# Gate_Drive.net
KiCad netlist of a schematic drawn in Altium Designer
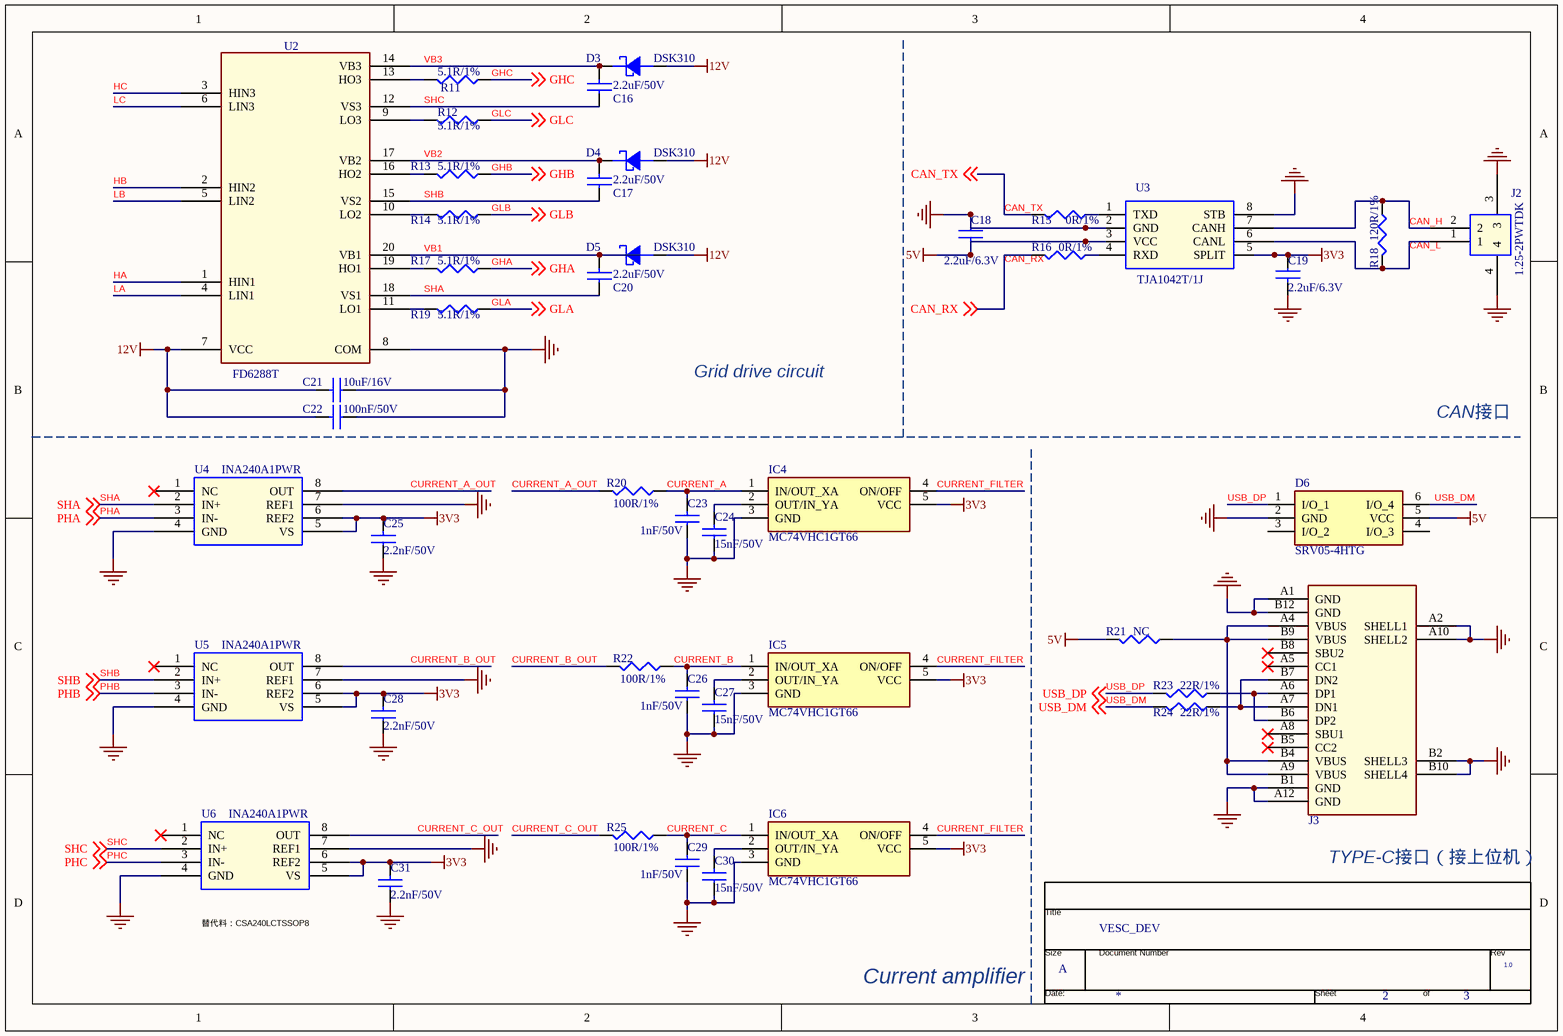
[diagram p0: Gate_Drive.SchDoc]

(export (version "E")
  (design (tool "Eeschema 10.0.6"))
  (components
    (comp (ref "C16") (value "2.2uF/50V") (footprint "C0603") (libsource (lib "*") (part "CAP NP")))
    (comp (ref "C17") (value "2.2uF/50V") (footprint "C0603") (libsource (lib "*") (part "CAP NP")))
    (comp (ref "C18") (value "2.2uF/6.3V") (footprint "C0402") (libsource (lib "*") (part "CAP NP")))
    (comp (ref "C19") (value "2.2uF/6.3V") (footprint "C0402") (libsource (lib "*") (part "CAP NP")))
    (comp (ref "C20") (value "2.2uF/50V") (footprint "C0603") (libsource (lib "*") (part "CAP NP")))
    (comp (ref "C21") (value "10uF/16V") (footprint "C0603") (libsource (lib "*") (part "CAP NP")))
    (comp (ref "C22") (value "100nF/50V") (footprint "C0402") (libsource (lib "*") (part "CAP NP")))
    (comp (ref "C23") (value "1nF/50V") (footprint "C0402") (libsource (lib "*") (part "CAP NP")))
    (comp (ref "C24") (value "15nF/50V") (footprint "C0402") (libsource (lib "*") (part "CAP NP")))
    (comp (ref "C25") (value "2.2nF/50V") (footprint "C0402") (libsource (lib "*") (part "CAP NP")))
    (comp (ref "C26") (value "1nF/50V") (footprint "C0402") (libsource (lib "*") (part "CAP NP")))
    (comp (ref "C27") (value "15nF/50V") (footprint "C0402") (libsource (lib "*") (part "CAP NP")))
    (comp (ref "C28") (value "2.2nF/50V") (footprint "C0402") (libsource (lib "*") (part "CAP NP")))
    (comp (ref "C29") (value "1nF/50V") (footprint "C0402") (libsource (lib "*") (part "CAP NP")))
    (comp (ref "C30") (value "15nF/50V") (footprint "C0402") (libsource (lib "*") (part "CAP NP")))
    (comp (ref "C31") (value "2.2nF/50V") (footprint "C0402") (libsource (lib "*") (part "CAP NP")))
    (comp (ref "D3") (value "DSK310") (footprint "SOD-123F") (libsource (lib "*") (part "DIODE SCHOTTKY21")))
    (comp (ref "D4") (value "DSK310") (footprint "SOD-123F") (libsource (lib "*") (part "DIODE SCHOTTKY21")))
    (comp (ref "D5") (value "DSK310") (footprint "SOD-123F") (libsource (lib "*") (part "DIODE SCHOTTKY21")))
    (comp (ref "D6")
      (value "SRV05-4HTG")
      (footprint "SamacSys:SOT95P280X145-6N")
      (description "TVS Diode (Uni-directional)")
      (fields (field (name "MOUSER PART NUMBER") "576-SRV05-4HTG"))
      (libsource (lib "VESC_DEVICE_Library") (part "SRV05-4HTG"))
    )
    (comp (ref "IC4")
      (value "MC74VHC1GT66")
      (footprint "SamacSys:SOT95P275X110-5N")
      (description "Integrated Circuit")
      (libsource (lib "VESC_DEVICE_Library") (part "MC74VHC1GT66"))
    )
    (comp (ref "IC5")
      (value "MC74VHC1GT66")
      (footprint "SamacSys:SOT95P275X110-5N")
      (description "Integrated Circuit")
      (libsource (lib "VESC_DEVICE_Library") (part "MC74VHC1GT66"))
    )
    (comp (ref "IC6")
      (value "MC74VHC1GT66")
      (footprint "SamacSys:SOT95P275X110-5N")
      (description "Integrated Circuit")
      (libsource (lib "VESC_DEVICE_Library") (part "MC74VHC1GT66"))
    )
    (comp (ref "J2")
      (value "1.25-2PWTDK")
      (footprint "SMD-2P-1_25")
      (libsource (lib "*") (part "1.25-2PWTDK"))
    )
    (comp (ref "J3")
      (value "TYPE-C 16PLC-H10.0")
      (footprint "TYPE-C-TH_16PLC-H10.0")
      (description "连接器类型:Type-C;标准:USB 3.1;公母:母;安装方式:直插;触点数量:16P;端口数量:1;额定电流 - 电源:5A;触头材质:-;触头镀层:-;工作温度范围:-40℃~+85℃;")
      (fields (field (name "MANUFACTURER") "SHOU HAN(首韩)"))
      (libsource (lib "VESC_DEVICE_Library") (part "TYPE-C 16PLC-H10.0"))
    )
    (comp (ref "R11") (value "5.1R/1%") (footprint "R0603") (libsource (lib "*") (part "RESISTOR")))
    (comp (ref "R12") (value "5.1R/1%") (footprint "R0603") (libsource (lib "*") (part "RESISTOR")))
    (comp (ref "R13") (value "5.1R/1%") (footprint "R0603") (libsource (lib "*") (part "RESISTOR")))
    (comp (ref "R14") (value "5.1R/1%") (footprint "R0603") (libsource (lib "*") (part "RESISTOR")))
    (comp (ref "R15") (value "0R/1%") (footprint "R0402") (libsource (lib "*") (part "RESISTOR")))
    (comp (ref "R16") (value "0R/1%") (footprint "R0402") (libsource (lib "*") (part "RESISTOR")))
    (comp (ref "R17") (value "5.1R/1%") (footprint "R0603") (libsource (lib "*") (part "RESISTOR")))
    (comp (ref "R18") (value "120R/1%") (footprint "R0402") (libsource (lib "*") (part "RESISTOR")))
    (comp (ref "R19") (value "5.1R/1%") (footprint "R0603") (libsource (lib "*") (part "RESISTOR")))
    (comp (ref "R20") (value "100R/1%") (footprint "R0402") (libsource (lib "*") (part "RESISTOR")))
    (comp (ref "R21") (value "NC") (footprint "R0603") (libsource (lib "*") (part "RESISTOR")))
    (comp (ref "R22") (value "100R/1%") (footprint "R0402") (libsource (lib "*") (part "RESISTOR")))
    (comp (ref "R23") (value "22R/1%") (footprint "R0402") (libsource (lib "*") (part "RESISTOR")))
    (comp (ref "R24") (value "22R/1%") (footprint "R0402") (libsource (lib "*") (part "RESISTOR")))
    (comp (ref "R25") (value "100R/1%") (footprint "R0402") (libsource (lib "*") (part "RESISTOR")))
    (comp (ref "U2")
      (value "FD6288T")
      (footprint "TSSOP-20")
      (libsource (lib "VESC_DEVICE_Library") (part "FD6288T"))
    )
    (comp (ref "U3") (value "TJA1042T/1J") (footprint "SOP-8") (libsource (lib "*") (part "TJA1042T/1J")))
    (comp (ref "U4") (value "INA240A1PWR") (footprint "TSSOP-8") (libsource (lib "*") (part "INA240A1PWR")))
    (comp (ref "U5") (value "INA240A1PWR") (footprint "TSSOP-8") (libsource (lib "*") (part "INA240A1PWR")))
    (comp (ref "U6") (value "INA240A1PWR") (footprint "TSSOP-8") (libsource (lib "*") (part "INA240A1PWR")))
  )
  (nets
    (net (code "1") (name "/CAN_H") (class "Default")
      (node (ref "J2") (pin "2") (pinfunction "2_2") (pintype "passive"))
      (node (ref "R18") (pin "1") (pinfunction "1_1") (pintype "passive"))
      (node (ref "U3") (pin "7") (pinfunction "CANH_7") (pintype "passive"))
    )
    (net (code "2") (name "/CAN_L") (class "Default")
      (node (ref "J2") (pin "1") (pinfunction "1_1") (pintype "passive"))
      (node (ref "R18") (pin "2") (pinfunction "2_2") (pintype "passive"))
      (node (ref "U3") (pin "6") (pinfunction "CANL_6") (pintype "passive"))
    )
    (net (code "3") (name "/CURRENT_A") (class "Default")
      (node (ref "C23") (pin "2") (pinfunction "2_2") (pintype "passive"))
      (node (ref "IC4") (pin "1") (pinfunction "IN/OUT_XA_1") (pintype "passive"))
      (node (ref "R20") (pin "1") (pinfunction "1_1") (pintype "passive"))
    )
    (net (code "4") (name "/CURRENT_A_OUT") (class "Default")
      (node (ref "R20") (pin "2") (pinfunction "2_2") (pintype "passive"))
      (node (ref "U4") (pin "8") (pinfunction "OUT_8") (pintype "passive"))
    )
    (net (code "5") (name "/CURRENT_B") (class "Default")
      (node (ref "C26") (pin "2") (pinfunction "2_2") (pintype "passive"))
      (node (ref "IC5") (pin "1") (pinfunction "IN/OUT_XA_1") (pintype "passive"))
      (node (ref "R22") (pin "1") (pinfunction "1_1") (pintype "passive"))
    )
    (net (code "6") (name "/CURRENT_B_OUT") (class "Default")
      (node (ref "R22") (pin "2") (pinfunction "2_2") (pintype "passive"))
      (node (ref "U5") (pin "8") (pinfunction "OUT_8") (pintype "passive"))
    )
    (net (code "7") (name "/CURRENT_C") (class "Default")
      (node (ref "C29") (pin "2") (pinfunction "2_2") (pintype "passive"))
      (node (ref "IC6") (pin "1") (pinfunction "IN/OUT_XA_1") (pintype "passive"))
      (node (ref "R25") (pin "1") (pinfunction "1_1") (pintype "passive"))
    )
    (net (code "8") (name "/CURRENT_C_OUT") (class "Default")
      (node (ref "R25") (pin "2") (pinfunction "2_2") (pintype "passive"))
      (node (ref "U6") (pin "8") (pinfunction "OUT_8") (pintype "passive"))
    )
    (net (code "9") (name "/CURRENT_FILTER") (class "Default")
      (node (ref "IC4") (pin "4") (pinfunction "ON/OFF_4") (pintype "passive"))
      (node (ref "IC5") (pin "4") (pinfunction "ON/OFF_4") (pintype "passive"))
      (node (ref "IC6") (pin "4") (pinfunction "ON/OFF_4") (pintype "passive"))
    )
    (net (code "10") (name "/HA") (class "Default")
      (node (ref "U2") (pin "1") (pinfunction "HIN1_1") (pintype "passive"))
    )
    (net (code "11") (name "/HB") (class "Default")
      (node (ref "U2") (pin "2") (pinfunction "HIN2_2") (pintype "passive"))
    )
    (net (code "12") (name "/HC") (class "Default")
      (node (ref "U2") (pin "3") (pinfunction "HIN3_3") (pintype "passive"))
    )
    (net (code "13") (name "/LA") (class "Default")
      (node (ref "U2") (pin "4") (pinfunction "LIN1_4") (pintype "passive"))
    )
    (net (code "14") (name "/LB") (class "Default")
      (node (ref "U2") (pin "5") (pinfunction "LIN2_5") (pintype "passive"))
    )
    (net (code "15") (name "/LC") (class "Default")
      (node (ref "U2") (pin "6") (pinfunction "LIN3_6") (pintype "passive"))
    )
    (net (code "16") (name "/VB1") (class "Default")
      (node (ref "C20") (pin "2") (pinfunction "2_2") (pintype "passive"))
      (node (ref "D5") (pin "1") (pinfunction "K_1") (pintype "passive"))
      (node (ref "U2") (pin "20") (pinfunction "VB1_20") (pintype "passive"))
    )
    (net (code "17") (name "/VB2") (class "Default")
      (node (ref "C17") (pin "2") (pinfunction "2_2") (pintype "passive"))
      (node (ref "D4") (pin "1") (pinfunction "K_1") (pintype "passive"))
      (node (ref "U2") (pin "17") (pinfunction "VB2_17") (pintype "passive"))
    )
    (net (code "18") (name "/VB3") (class "Default")
      (node (ref "C16") (pin "2") (pinfunction "2_2") (pintype "passive"))
      (node (ref "D3") (pin "1") (pinfunction "K_1") (pintype "passive"))
      (node (ref "U2") (pin "14") (pinfunction "VB3_14") (pintype "passive"))
    )
    (net (code "19") (name "3V3") (class "Default")
      (node (ref "C19") (pin "1") (pinfunction "1_1") (pintype "passive"))
      (node (ref "C25") (pin "2") (pinfunction "2_2") (pintype "passive"))
      (node (ref "C28") (pin "2") (pinfunction "2_2") (pintype "passive"))
      (node (ref "C31") (pin "2") (pinfunction "2_2") (pintype "passive"))
      (node (ref "IC4") (pin "5") (pinfunction "VCC_5") (pintype "passive"))
      (node (ref "IC5") (pin "5") (pinfunction "VCC_5") (pintype "passive"))
      (node (ref "IC6") (pin "5") (pinfunction "VCC_5") (pintype "passive"))
      (node (ref "U3") (pin "5") (pinfunction "SPLIT_5") (pintype "passive"))
      (node (ref "U4") (pin "5") (pinfunction "VS_5") (pintype "passive"))
      (node (ref "U4") (pin "6") (pinfunction "REF2_6") (pintype "passive"))
      (node (ref "U5") (pin "5") (pinfunction "VS_5") (pintype "passive"))
      (node (ref "U5") (pin "6") (pinfunction "REF2_6") (pintype "passive"))
      (node (ref "U6") (pin "5") (pinfunction "VS_5") (pintype "passive"))
      (node (ref "U6") (pin "6") (pinfunction "REF2_6") (pintype "passive"))
    )
    (net (code "20") (name "5V") (class "Default")
      (node (ref "C18") (pin "2") (pinfunction "2_2") (pintype "passive"))
      (node (ref "D6") (pin "5") (pinfunction "VCC_5") (pintype "passive"))
      (node (ref "R21") (pin "2") (pinfunction "2_2") (pintype "passive"))
      (node (ref "U3") (pin "3") (pinfunction "VCC_3") (pintype "passive"))
    )
    (net (code "21") (name "12V") (class "Default")
      (node (ref "C21") (pin "2") (pinfunction "2_2") (pintype "passive"))
      (node (ref "C22") (pin "2") (pinfunction "2_2") (pintype "passive"))
      (node (ref "D3") (pin "2") (pinfunction "A_2") (pintype "passive"))
      (node (ref "D4") (pin "2") (pinfunction "A_2") (pintype "passive"))
      (node (ref "D5") (pin "2") (pinfunction "A_2") (pintype "passive"))
      (node (ref "U2") (pin "7") (pinfunction "VCC_7") (pintype "power_in"))
    )
    (net (code "22") (name "CAN_RX") (class "Default")
      (node (ref "R16") (pin "2") (pinfunction "2_2") (pintype "passive"))
    )
    (net (code "23") (name "CAN_TX") (class "Default")
      (node (ref "R15") (pin "2") (pinfunction "2_2") (pintype "passive"))
    )
    (net (code "24") (name "GHA") (class "Default")
      (node (ref "R17") (pin "1") (pinfunction "1_1") (pintype "passive"))
    )
    (net (code "25") (name "GHB") (class "Default")
      (node (ref "R13") (pin "1") (pinfunction "1_1") (pintype "passive"))
    )
    (net (code "26") (name "GHC") (class "Default")
      (node (ref "R11") (pin "1") (pinfunction "1_1") (pintype "passive"))
    )
    (net (code "27") (name "GLA") (class "Default")
      (node (ref "R19") (pin "1") (pinfunction "1_1") (pintype "passive"))
    )
    (net (code "28") (name "GLB") (class "Default")
      (node (ref "R14") (pin "1") (pinfunction "1_1") (pintype "passive"))
    )
    (net (code "29") (name "GLC") (class "Default")
      (node (ref "R12") (pin "1") (pinfunction "1_1") (pintype "passive"))
    )
    (net (code "30") (name "GND") (class "Default")
      (node (ref "C18") (pin "1") (pinfunction "1_1") (pintype "passive"))
      (node (ref "C19") (pin "2") (pinfunction "2_2") (pintype "passive"))
      (node (ref "C21") (pin "1") (pinfunction "1_1") (pintype "passive"))
      (node (ref "C22") (pin "1") (pinfunction "1_1") (pintype "passive"))
      (node (ref "C23") (pin "1") (pinfunction "1_1") (pintype "passive"))
      (node (ref "C24") (pin "1") (pinfunction "1_1") (pintype "passive"))
      (node (ref "C25") (pin "1") (pinfunction "1_1") (pintype "passive"))
      (node (ref "C26") (pin "1") (pinfunction "1_1") (pintype "passive"))
      (node (ref "C27") (pin "1") (pinfunction "1_1") (pintype "passive"))
      (node (ref "C28") (pin "1") (pinfunction "1_1") (pintype "passive"))
      (node (ref "C29") (pin "1") (pinfunction "1_1") (pintype "passive"))
      (node (ref "C30") (pin "1") (pinfunction "1_1") (pintype "passive"))
      (node (ref "C31") (pin "1") (pinfunction "1_1") (pintype "passive"))
      (node (ref "D6") (pin "2") (pinfunction "GND_2") (pintype "passive"))
      (node (ref "IC4") (pin "3") (pinfunction "GND_3") (pintype "passive"))
      (node (ref "IC5") (pin "3") (pinfunction "GND_3") (pintype "passive"))
      (node (ref "IC6") (pin "3") (pinfunction "GND_3") (pintype "passive"))
      (node (ref "J2") (pin "3") (pinfunction "3_3") (pintype "passive"))
      (node (ref "J2") (pin "4") (pinfunction "4_4") (pintype "passive"))
      (node (ref "J3") (pin "A1") (pinfunction "GND_A1") (pintype "power_in"))
      (node (ref "J3") (pin "A10") (pinfunction "SHELL2_A10") (pintype "power_in"))
      (node (ref "J3") (pin "A12") (pinfunction "GND_A12") (pintype "power_in"))
      (node (ref "J3") (pin "A2") (pinfunction "SHELL1_A2") (pintype "power_in"))
      (node (ref "J3") (pin "B1") (pinfunction "GND_B1") (pintype "power_in"))
      (node (ref "J3") (pin "B10") (pinfunction "SHELL4_B10") (pintype "power_in"))
      (node (ref "J3") (pin "B12") (pinfunction "GND_B12") (pintype "power_in"))
      (node (ref "J3") (pin "B2") (pinfunction "SHELL3_B2") (pintype "power_in"))
      (node (ref "U2") (pin "8") (pinfunction "COM_8") (pintype "power_in"))
      (node (ref "U3") (pin "2") (pinfunction "GND_2") (pintype "passive"))
      (node (ref "U3") (pin "8") (pinfunction "STB_8") (pintype "passive"))
      (node (ref "U4") (pin "4") (pinfunction "GND_4") (pintype "passive"))
      (node (ref "U4") (pin "7") (pinfunction "REF1_7") (pintype "passive"))
      (node (ref "U5") (pin "4") (pinfunction "GND_4") (pintype "passive"))
      (node (ref "U5") (pin "7") (pinfunction "REF1_7") (pintype "passive"))
      (node (ref "U6") (pin "4") (pinfunction "GND_4") (pintype "passive"))
      (node (ref "U6") (pin "7") (pinfunction "REF1_7") (pintype "passive"))
    )
    (net (code "31") (name "Net-(IC4-OUT{slash}IN_YA)") (class "Default")
      (node (ref "C24") (pin "2") (pinfunction "2_2") (pintype "passive"))
      (node (ref "IC4") (pin "2") (pinfunction "OUT/IN_YA_2") (pintype "passive"))
    )
    (net (code "32") (name "Net-(IC5-OUT{slash}IN_YA)") (class "Default")
      (node (ref "C27") (pin "2") (pinfunction "2_2") (pintype "passive"))
      (node (ref "IC5") (pin "2") (pinfunction "OUT/IN_YA_2") (pintype "passive"))
    )
    (net (code "33") (name "Net-(IC6-OUT{slash}IN_YA)") (class "Default")
      (node (ref "C30") (pin "2") (pinfunction "2_2") (pintype "passive"))
      (node (ref "IC6") (pin "2") (pinfunction "OUT/IN_YA_2") (pintype "passive"))
    )
    (net (code "34") (name "Net-(J3-DN1)") (class "Default")
      (node (ref "J3") (pin "A7") (pinfunction "DN1_A7") (pintype "passive"))
      (node (ref "J3") (pin "B7") (pinfunction "DN2_B7") (pintype "passive"))
      (node (ref "R24") (pin "1") (pinfunction "1_1") (pintype "passive"))
    )
    (net (code "35") (name "Net-(J3-DP1)") (class "Default")
      (node (ref "J3") (pin "A6") (pinfunction "DP1_A6") (pintype "passive"))
      (node (ref "J3") (pin "B6") (pinfunction "DP2_B6") (pintype "passive"))
      (node (ref "R23") (pin "1") (pinfunction "1_1") (pintype "passive"))
    )
    (net (code "36") (name "Net-(J3-VBUS-PadA4)") (class "Default")
      (node (ref "J3") (pin "A4") (pinfunction "VBUS_A4") (pintype "power_in"))
      (node (ref "J3") (pin "A9") (pinfunction "VBUS_A9") (pintype "power_in"))
      (node (ref "J3") (pin "B4") (pinfunction "VBUS_B4") (pintype "power_in"))
      (node (ref "J3") (pin "B9") (pinfunction "VBUS_B9") (pintype "power_in"))
      (node (ref "R21") (pin "1") (pinfunction "1_1") (pintype "passive"))
    )
    (net (code "37") (name "Net-(U2-HO1)") (class "Default")
      (node (ref "R17") (pin "2") (pinfunction "2_2") (pintype "passive"))
      (node (ref "U2") (pin "19") (pinfunction "HO1_19") (pintype "passive"))
    )
    (net (code "38") (name "Net-(U2-HO2)") (class "Default")
      (node (ref "R13") (pin "2") (pinfunction "2_2") (pintype "passive"))
      (node (ref "U2") (pin "16") (pinfunction "HO2_16") (pintype "passive"))
    )
    (net (code "39") (name "Net-(U2-HO3)") (class "Default")
      (node (ref "R11") (pin "2") (pinfunction "2_2") (pintype "passive"))
      (node (ref "U2") (pin "13") (pinfunction "HO3_13") (pintype "passive"))
    )
    (net (code "40") (name "Net-(U2-LO1)") (class "Default")
      (node (ref "R19") (pin "2") (pinfunction "2_2") (pintype "passive"))
      (node (ref "U2") (pin "11") (pinfunction "LO1_11") (pintype "passive"))
    )
    (net (code "41") (name "Net-(U2-LO2)") (class "Default")
      (node (ref "R14") (pin "2") (pinfunction "2_2") (pintype "passive"))
      (node (ref "U2") (pin "10") (pinfunction "LO2_10") (pintype "passive"))
    )
    (net (code "42") (name "Net-(U2-LO3)") (class "Default")
      (node (ref "R12") (pin "2") (pinfunction "2_2") (pintype "passive"))
      (node (ref "U2") (pin "9") (pinfunction "LO3_9") (pintype "passive"))
    )
    (net (code "43") (name "Net-(U3-RXD)") (class "Default")
      (node (ref "R16") (pin "1") (pinfunction "1_1") (pintype "passive"))
      (node (ref "U3") (pin "4") (pinfunction "RXD_4") (pintype "passive"))
    )
    (net (code "44") (name "Net-(U3-TXD)") (class "Default")
      (node (ref "R15") (pin "1") (pinfunction "1_1") (pintype "passive"))
      (node (ref "U3") (pin "1") (pinfunction "TXD_1") (pintype "passive"))
    )
    (net (code "45") (name "PHA") (class "Default")
      (node (ref "U4") (pin "3") (pinfunction "IN-_3") (pintype "passive"))
    )
    (net (code "46") (name "PHB") (class "Default")
      (node (ref "U5") (pin "3") (pinfunction "IN-_3") (pintype "passive"))
    )
    (net (code "47") (name "PHC") (class "Default")
      (node (ref "U6") (pin "3") (pinfunction "IN-_3") (pintype "passive"))
    )
    (net (code "48") (name "SHA") (class "Default")
      (node (ref "C20") (pin "1") (pinfunction "1_1") (pintype "passive"))
      (node (ref "U2") (pin "18") (pinfunction "VS1_18") (pintype "passive"))
      (node (ref "U4") (pin "2") (pinfunction "IN+_2") (pintype "passive"))
    )
    (net (code "49") (name "SHB") (class "Default")
      (node (ref "C17") (pin "1") (pinfunction "1_1") (pintype "passive"))
      (node (ref "U2") (pin "15") (pinfunction "VS2_15") (pintype "passive"))
      (node (ref "U5") (pin "2") (pinfunction "IN+_2") (pintype "passive"))
    )
    (net (code "50") (name "SHC") (class "Default")
      (node (ref "C16") (pin "1") (pinfunction "1_1") (pintype "passive"))
      (node (ref "U2") (pin "12") (pinfunction "VS3_12") (pintype "passive"))
      (node (ref "U6") (pin "2") (pinfunction "IN+_2") (pintype "passive"))
    )
    (net (code "51") (name "USB_DM") (class "Default")
      (node (ref "D6") (pin "6") (pinfunction "I/O_4_6") (pintype "passive"))
      (node (ref "R24") (pin "2") (pinfunction "2_2") (pintype "passive"))
    )
    (net (code "52") (name "USB_DP") (class "Default")
      (node (ref "D6") (pin "1") (pinfunction "I/O_1_1") (pintype "passive"))
      (node (ref "R23") (pin "2") (pinfunction "2_2") (pintype "passive"))
    )
    (net (code "53") (name "unconnected-(D6-I{slash}O_2-Pad3)") (class "Default")
      (node (ref "D6") (pin "3") (pinfunction "I/O_2_3") (pintype "passive"))
    )
    (net (code "54") (name "unconnected-(D6-I{slash}O_3-Pad4)") (class "Default")
      (node (ref "D6") (pin "4") (pinfunction "I/O_3_4") (pintype "passive"))
    )
    (net (code "55") (name "unconnected-(J3-CC1-PadA5)") (class "Default")
      (node (ref "J3") (pin "A5") (pinfunction "CC1_A5") (pintype "passive+no_connect"))
    )
    (net (code "56") (name "unconnected-(J3-CC2-PadB5)") (class "Default")
      (node (ref "J3") (pin "B5") (pinfunction "CC2_B5") (pintype "passive+no_connect"))
    )
    (net (code "57") (name "unconnected-(J3-SBU1-PadA8)") (class "Default")
      (node (ref "J3") (pin "A8") (pinfunction "SBU1_A8") (pintype "passive+no_connect"))
    )
    (net (code "58") (name "unconnected-(J3-SBU2-PadB8)") (class "Default")
      (node (ref "J3") (pin "B8") (pinfunction "SBU2_B8") (pintype "passive+no_connect"))
    )
    (net (code "59") (name "unconnected-(U4-NC-Pad1)") (class "Default")
      (node (ref "U4") (pin "1") (pinfunction "NC_1") (pintype "passive+no_connect"))
    )
    (net (code "60") (name "unconnected-(U5-NC-Pad1)") (class "Default")
      (node (ref "U5") (pin "1") (pinfunction "NC_1") (pintype "passive+no_connect"))
    )
    (net (code "61") (name "unconnected-(U6-NC-Pad1)") (class "Default")
      (node (ref "U6") (pin "1") (pinfunction "NC_1") (pintype "passive+no_connect"))
    )
  )
)
